# BMS_Interface.net
KiCad netlist of a schematic drawn in EAGLE
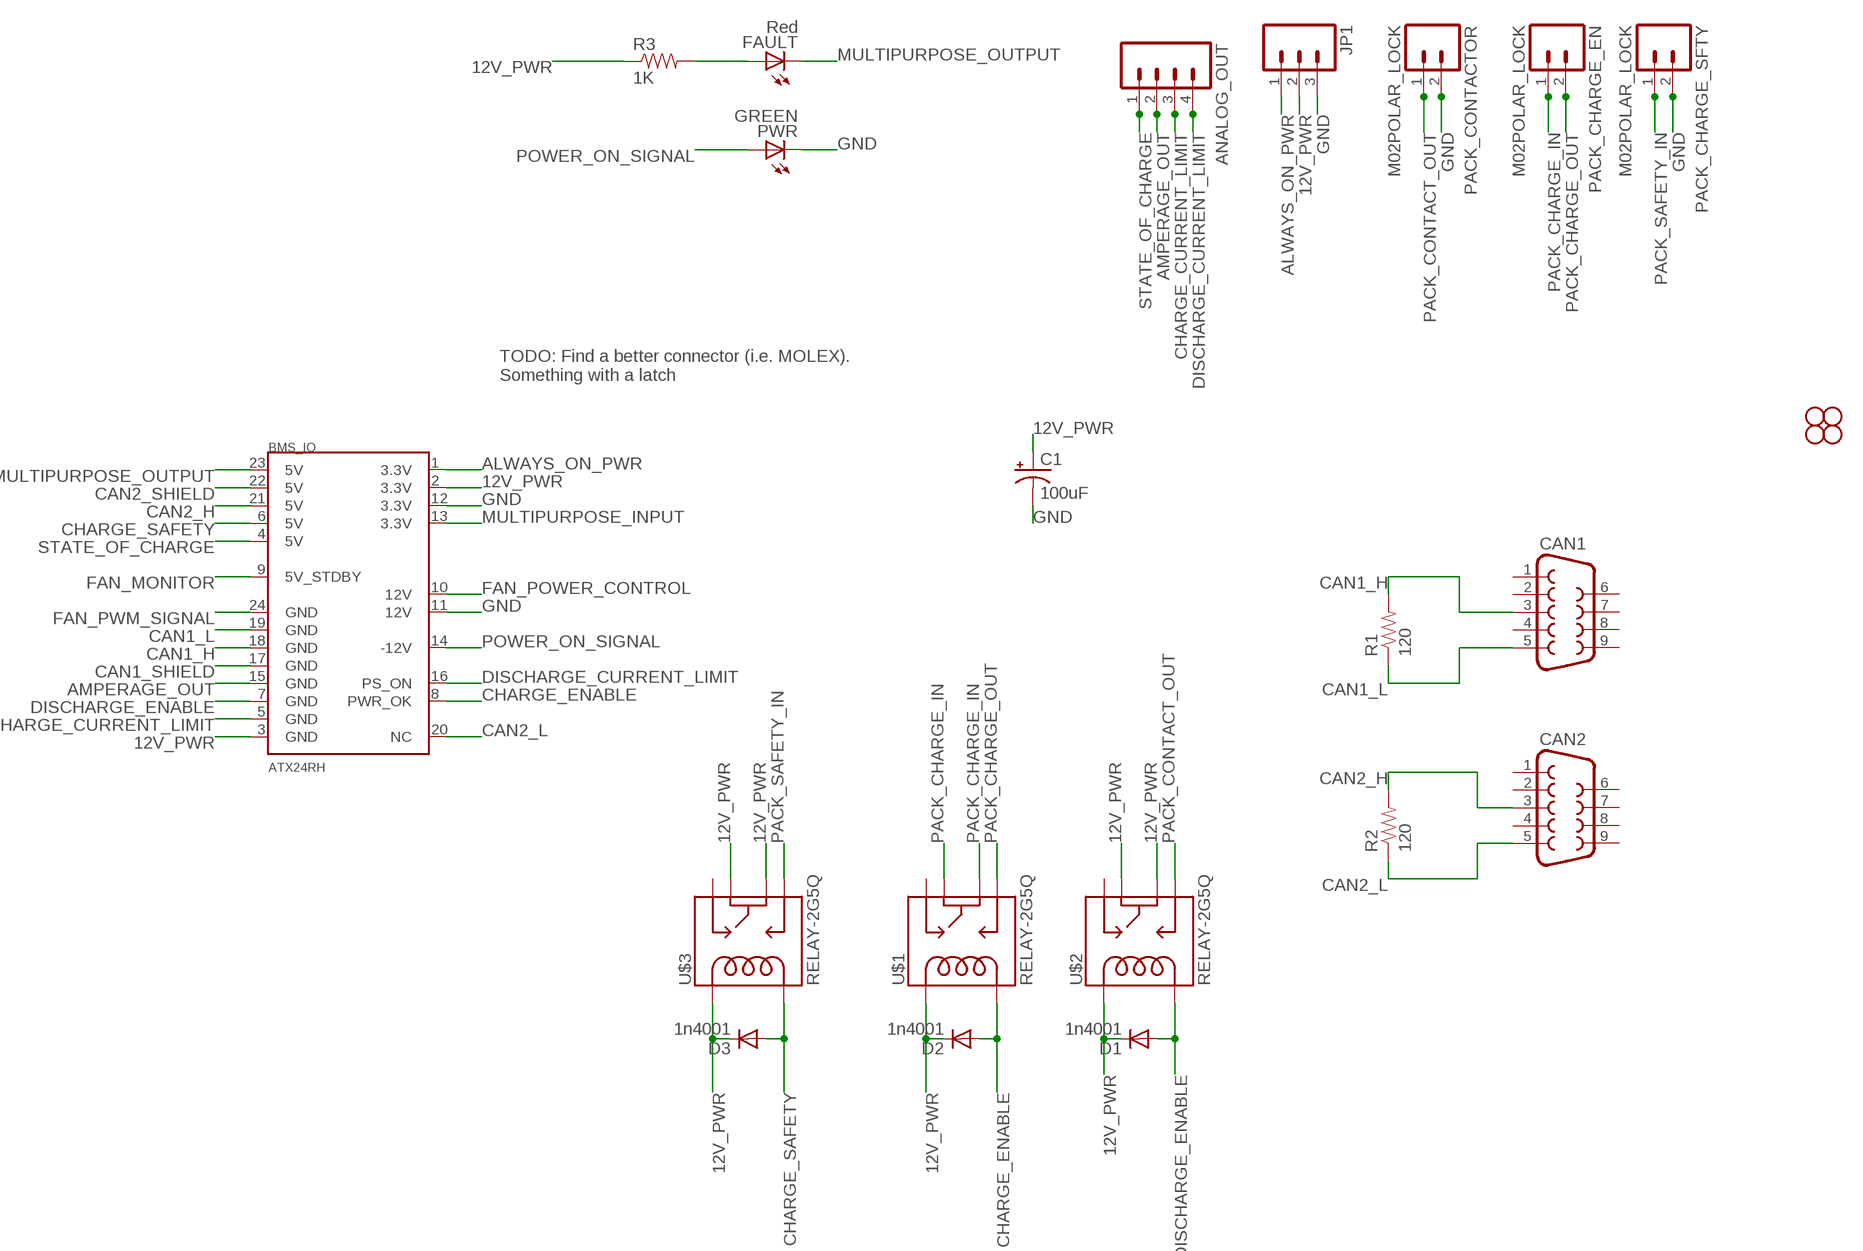
[diagram p0: schematic, sheet 1]

(export (version "E")
  (design (tool "Eeschema 10.0.6"))
  (components
    (comp (ref "ANALOG_OUT")
      (value "M04POLAR_LOCK")
      (footprint "eagle-import:MOLEX-1X4_LOCK")
      (libsource (lib "eagle-import") (part "M04POLAR_LOCK"))
    )
    (comp (ref "BMS_IO")
      (value "ATX24RH")
      (footprint "eagle-import:ATX24_RIGHT_ANGLE")
      (libsource (lib "eagle-import") (part "ATX24RH"))
    )
    (comp (ref "C1")
      (value "100uF")
      (footprint "eagle-import:CPOL-RADIAL-100UF-25V")
      (libsource (lib "eagle-import") (part "CAP_POLPTH1"))
    )
    (comp (ref "CAN1")
      (value "DB9FEMALE")
      (footprint "eagle-import:DB9")
      (libsource (lib "eagle-import") (part "DB9FEMALE"))
    )
    (comp (ref "CAN2")
      (value "DB9FEMALE")
      (footprint "eagle-import:DB9")
      (libsource (lib "eagle-import") (part "DB9FEMALE"))
    )
    (comp (ref "D1")
      (value "1n4001")
      (footprint "eagle-import:SMA-DIODE")
      (libsource (lib "eagle-import") (part "DIODESMA"))
    )
    (comp (ref "D2")
      (value "1n4001")
      (footprint "eagle-import:SMA-DIODE")
      (libsource (lib "eagle-import") (part "DIODESMA"))
    )
    (comp (ref "D3")
      (value "1n4001")
      (footprint "eagle-import:SMA-DIODE")
      (libsource (lib "eagle-import") (part "DIODESMA"))
    )
    (comp (ref "FAULT")
      (value "Red")
      (footprint "eagle-import:LED5MM")
      (libsource (lib "eagle-import") (part "LED5MM"))
    )
    (comp (ref "JP1")
      (value "M03SCREW")
      (footprint "eagle-import:SCREWTERMINAL-3.5MM-3")
      (libsource (lib "eagle-import") (part "M03SCREW"))
    )
    (comp (ref "PACK_CHARGE_EN")
      (value "M02POLAR_LOCK")
      (footprint "eagle-import:MOLEX-1X2_LOCK")
      (libsource (lib "eagle-import") (part "M02POLAR_LOCK"))
    )
    (comp (ref "PACK_CHARGE_SFTY")
      (value "M02POLAR_LOCK")
      (footprint "eagle-import:MOLEX-1X2_LOCK")
      (libsource (lib "eagle-import") (part "M02POLAR_LOCK"))
    )
    (comp (ref "PACK_CONTACTOR")
      (value "M02POLAR_LOCK")
      (footprint "eagle-import:MOLEX-1X2_LOCK")
      (libsource (lib "eagle-import") (part "M02POLAR_LOCK"))
    )
    (comp (ref "PWR")
      (value "GREEN")
      (footprint "eagle-import:LED5MM")
      (libsource (lib "eagle-import") (part "LED5MM"))
    )
    (comp (ref "R1")
      (value "120")
      (footprint "eagle-import:0603-RES")
      (libsource (lib "eagle-import") (part "RESISTOR0603"))
    )
    (comp (ref "R2")
      (value "120")
      (footprint "eagle-import:0603-RES")
      (libsource (lib "eagle-import") (part "RESISTOR0603"))
    )
    (comp (ref "R3")
      (value "1K")
      (footprint "eagle-import:0805")
      (libsource (lib "eagle-import") (part "RESISTOR0805-RES"))
    )
    (comp (ref "STANDOFF1")
      (value "STAND-OFF")
      (footprint "eagle-import:STAND-OFF")
      (libsource (lib "eagle-import") (part "STAND-OFF"))
    )
    (comp (ref "STANDOFF2")
      (value "STAND-OFF")
      (footprint "eagle-import:STAND-OFF")
      (libsource (lib "eagle-import") (part "STAND-OFF"))
    )
    (comp (ref "STANDOFF3")
      (value "STAND-OFF")
      (footprint "eagle-import:STAND-OFF")
      (libsource (lib "eagle-import") (part "STAND-OFF"))
    )
    (comp (ref "STANDOFF4")
      (value "STAND-OFF")
      (footprint "eagle-import:STAND-OFF")
      (libsource (lib "eagle-import") (part "STAND-OFF"))
    )
    (comp (ref "U$1")
      (value "RELAY-2G5Q")
      (footprint "eagle-import:RELAY-G5V")
      (libsource (lib "eagle-import") (part "RELAY-2G5Q"))
    )
    (comp (ref "U$2")
      (value "RELAY-2G5Q")
      (footprint "eagle-import:RELAY-G5V")
      (libsource (lib "eagle-import") (part "RELAY-2G5Q"))
    )
    (comp (ref "U$3")
      (value "RELAY-2G5Q")
      (footprint "eagle-import:RELAY-G5V")
      (libsource (lib "eagle-import") (part "RELAY-2G5Q"))
    )
  )
  (nets
    (net (code "1") (name "/12V_PWR") (class "Default")
      (node (ref "BMS_IO") (pin "2") (pinfunction "3.3V_2") (pintype "bidirectional"))
      (node (ref "BMS_IO") (pin "3") (pinfunction "GND_3") (pintype "bidirectional"))
      (node (ref "C1") (pin "1") (pinfunction "+_1") (pintype "passive"))
      (node (ref "D1") (pin "C") (pinfunction "C_C") (pintype "passive"))
      (node (ref "D2") (pin "C") (pinfunction "C_C") (pintype "passive"))
      (node (ref "D3") (pin "C") (pinfunction "C_C") (pintype "passive"))
      (node (ref "JP1") (pin "2") (pinfunction "2_2") (pintype "passive"))
      (node (ref "R3") (pin "1") (pinfunction "1_1") (pintype "passive"))
      (node (ref "U$1") (pin "2") (pinfunction "2_2") (pintype "bidirectional"))
      (node (ref "U$2") (pin "2") (pinfunction "2_2") (pintype "bidirectional"))
      (node (ref "U$2") (pin "5") (pinfunction "5_5") (pintype "bidirectional"))
      (node (ref "U$2") (pin "6") (pinfunction "6_6") (pintype "bidirectional"))
      (node (ref "U$3") (pin "2") (pinfunction "2_2") (pintype "bidirectional"))
      (node (ref "U$3") (pin "5") (pinfunction "5_5") (pintype "bidirectional"))
      (node (ref "U$3") (pin "6") (pinfunction "6_6") (pintype "bidirectional"))
    )
    (net (code "2") (name "/ALWAYS_ON_PWR") (class "Default")
      (node (ref "BMS_IO") (pin "1") (pinfunction "3.3V_1") (pintype "bidirectional"))
      (node (ref "JP1") (pin "1") (pinfunction "1_1") (pintype "passive"))
    )
    (net (code "3") (name "/AMPERAGE_OUT") (class "Default")
      (node (ref "ANALOG_OUT") (pin "2") (pinfunction "2_2") (pintype "passive"))
      (node (ref "BMS_IO") (pin "15") (pinfunction "GND_15") (pintype "bidirectional"))
    )
    (net (code "4") (name "/CAN1_H") (class "Default")
      (node (ref "BMS_IO") (pin "18") (pinfunction "GND_18") (pintype "bidirectional"))
      (node (ref "CAN1") (pin "3") (pinfunction "3_3") (pintype "passive"))
      (node (ref "R1") (pin "2") (pinfunction "2_2") (pintype "passive"))
    )
    (net (code "5") (name "/CAN1_L") (class "Default")
      (node (ref "BMS_IO") (pin "19") (pinfunction "GND_19") (pintype "bidirectional"))
      (node (ref "CAN1") (pin "5") (pinfunction "5_5") (pintype "passive"))
      (node (ref "R1") (pin "1") (pinfunction "1_1") (pintype "passive"))
    )
    (net (code "6") (name "/CAN1_SHIELD") (class "Default")
      (node (ref "BMS_IO") (pin "17") (pinfunction "GND_17") (pintype "bidirectional"))
    )
    (net (code "7") (name "/CAN2_H") (class "Default")
      (node (ref "BMS_IO") (pin "21") (pinfunction "5V_21") (pintype "bidirectional"))
      (node (ref "CAN2") (pin "3") (pinfunction "3_3") (pintype "passive"))
      (node (ref "R2") (pin "2") (pinfunction "2_2") (pintype "passive"))
    )
    (net (code "8") (name "/CAN2_L") (class "Default")
      (node (ref "BMS_IO") (pin "20") (pinfunction "NC_20") (pintype "bidirectional"))
      (node (ref "CAN2") (pin "5") (pinfunction "5_5") (pintype "passive"))
      (node (ref "R2") (pin "1") (pinfunction "1_1") (pintype "passive"))
    )
    (net (code "9") (name "/CAN2_SHIELD") (class "Default")
      (node (ref "BMS_IO") (pin "22") (pinfunction "5V_22") (pintype "bidirectional"))
    )
    (net (code "10") (name "/CHARGE_CURRENT_LIMIT") (class "Default")
      (node (ref "ANALOG_OUT") (pin "3") (pinfunction "3_3") (pintype "passive"))
      (node (ref "BMS_IO") (pin "5") (pinfunction "GND_5") (pintype "bidirectional"))
    )
    (net (code "11") (name "/CHARGE_ENABLE") (class "Default")
      (node (ref "BMS_IO") (pin "8") (pinfunction "PWR_OK_8") (pintype "bidirectional"))
      (node (ref "D2") (pin "A") (pinfunction "A_A") (pintype "passive"))
      (node (ref "U$1") (pin "9") (pinfunction "9_9") (pintype "bidirectional"))
    )
    (net (code "12") (name "/CHARGE_SAFETY") (class "Default")
      (node (ref "BMS_IO") (pin "6") (pinfunction "5V_6") (pintype "bidirectional"))
      (node (ref "D3") (pin "A") (pinfunction "A_A") (pintype "passive"))
      (node (ref "U$3") (pin "9") (pinfunction "9_9") (pintype "bidirectional"))
    )
    (net (code "13") (name "/DISCHARGE_CURRENT_LIMIT") (class "Default")
      (node (ref "ANALOG_OUT") (pin "4") (pinfunction "4_4") (pintype "passive"))
      (node (ref "BMS_IO") (pin "16") (pinfunction "PS_ON_16") (pintype "bidirectional"))
    )
    (net (code "14") (name "/DISCHARGE_ENABLE") (class "Default")
      (node (ref "BMS_IO") (pin "7") (pinfunction "GND_7") (pintype "bidirectional"))
      (node (ref "D1") (pin "A") (pinfunction "A_A") (pintype "passive"))
      (node (ref "U$2") (pin "9") (pinfunction "9_9") (pintype "bidirectional"))
    )
    (net (code "15") (name "/FAN_MONITOR") (class "Default")
      (node (ref "BMS_IO") (pin "9") (pinfunction "5V_STDBY_9") (pintype "bidirectional"))
    )
    (net (code "16") (name "/FAN_POWER_CONTROL") (class "Default")
      (node (ref "BMS_IO") (pin "10") (pinfunction "12V_10") (pintype "bidirectional"))
    )
    (net (code "17") (name "/FAN_PWM_SIGNAL") (class "Default")
      (node (ref "BMS_IO") (pin "24") (pinfunction "GND_24") (pintype "bidirectional"))
    )
    (net (code "18") (name "/GND") (class "Default")
      (node (ref "BMS_IO") (pin "11") (pinfunction "12V_11") (pintype "bidirectional"))
      (node (ref "BMS_IO") (pin "12") (pinfunction "3.3V_12") (pintype "bidirectional"))
      (node (ref "C1") (pin "2") (pinfunction "-_2") (pintype "passive"))
      (node (ref "JP1") (pin "3") (pinfunction "3_3") (pintype "passive"))
      (node (ref "PACK_CHARGE_SFTY") (pin "2") (pinfunction "2_2") (pintype "passive"))
      (node (ref "PACK_CONTACTOR") (pin "2") (pinfunction "2_2") (pintype "passive"))
      (node (ref "PWR") (pin "K") (pinfunction "C_K") (pintype "passive"))
    )
    (net (code "19") (name "/MULTIPURPOSE_INPUT") (class "Default")
      (node (ref "BMS_IO") (pin "13") (pinfunction "3.3V_13") (pintype "bidirectional"))
    )
    (net (code "20") (name "/MULTIPURPOSE_OUTPUT") (class "Default")
      (node (ref "BMS_IO") (pin "23") (pinfunction "5V_23") (pintype "bidirectional"))
      (node (ref "FAULT") (pin "K") (pinfunction "C_K") (pintype "passive"))
    )
    (net (code "21") (name "/PACK_CHARGE_IN") (class "Default")
      (node (ref "PACK_CHARGE_EN") (pin "1") (pinfunction "1_1") (pintype "passive"))
      (node (ref "U$1") (pin "5") (pinfunction "5_5") (pintype "bidirectional"))
      (node (ref "U$1") (pin "6") (pinfunction "6_6") (pintype "bidirectional"))
    )
    (net (code "22") (name "/PACK_CHARGE_OUT") (class "Default")
      (node (ref "PACK_CHARGE_EN") (pin "2") (pinfunction "2_2") (pintype "passive"))
      (node (ref "U$1") (pin "10") (pinfunction "10_10") (pintype "bidirectional"))
    )
    (net (code "23") (name "/PACK_CONTACT_OUT") (class "Default")
      (node (ref "PACK_CONTACTOR") (pin "1") (pinfunction "1_1") (pintype "passive"))
      (node (ref "U$2") (pin "10") (pinfunction "10_10") (pintype "bidirectional"))
    )
    (net (code "24") (name "/PACK_SAFETY_IN") (class "Default")
      (node (ref "PACK_CHARGE_SFTY") (pin "1") (pinfunction "1_1") (pintype "passive"))
      (node (ref "U$3") (pin "10") (pinfunction "10_10") (pintype "bidirectional"))
    )
    (net (code "25") (name "/POWER_ON_SIGNAL") (class "Default")
      (node (ref "BMS_IO") (pin "14") (pinfunction "-12V_14") (pintype "bidirectional"))
      (node (ref "PWR") (pin "A") (pinfunction "A_A") (pintype "passive"))
    )
    (net (code "26") (name "/STATE_OF_CHARGE") (class "Default")
      (node (ref "ANALOG_OUT") (pin "1") (pinfunction "1_1") (pintype "passive"))
      (node (ref "BMS_IO") (pin "4") (pinfunction "5V_4") (pintype "bidirectional"))
    )
    (net (code "27") (name "Net-(FAULT-PadA)") (class "Default")
      (node (ref "FAULT") (pin "A") (pinfunction "A_A") (pintype "passive"))
      (node (ref "R3") (pin "2") (pinfunction "2_2") (pintype "passive"))
    )
    (net (code "28") (name "unconnected-(CAN1-Pad1)") (class "Default")
      (node (ref "CAN1") (pin "1") (pinfunction "1_1") (pintype "passive"))
    )
    (net (code "29") (name "unconnected-(CAN1-Pad2)") (class "Default")
      (node (ref "CAN1") (pin "2") (pinfunction "2_2") (pintype "passive"))
    )
    (net (code "30") (name "unconnected-(CAN1-Pad4)") (class "Default")
      (node (ref "CAN1") (pin "4") (pinfunction "4_4") (pintype "passive"))
    )
    (net (code "31") (name "unconnected-(CAN1-Pad6)") (class "Default")
      (node (ref "CAN1") (pin "6") (pinfunction "6_6") (pintype "passive"))
    )
    (net (code "32") (name "unconnected-(CAN1-Pad7)") (class "Default")
      (node (ref "CAN1") (pin "7") (pinfunction "7_7") (pintype "passive"))
    )
    (net (code "33") (name "unconnected-(CAN1-Pad8)") (class "Default")
      (node (ref "CAN1") (pin "8") (pinfunction "8_8") (pintype "passive"))
    )
    (net (code "34") (name "unconnected-(CAN1-Pad9)") (class "Default")
      (node (ref "CAN1") (pin "9") (pinfunction "9_9") (pintype "passive"))
    )
    (net (code "35") (name "unconnected-(CAN2-Pad1)") (class "Default")
      (node (ref "CAN2") (pin "1") (pinfunction "1_1") (pintype "passive"))
    )
    (net (code "36") (name "unconnected-(CAN2-Pad2)") (class "Default")
      (node (ref "CAN2") (pin "2") (pinfunction "2_2") (pintype "passive"))
    )
    (net (code "37") (name "unconnected-(CAN2-Pad4)") (class "Default")
      (node (ref "CAN2") (pin "4") (pinfunction "4_4") (pintype "passive"))
    )
    (net (code "38") (name "unconnected-(CAN2-Pad6)") (class "Default")
      (node (ref "CAN2") (pin "6") (pinfunction "6_6") (pintype "passive"))
    )
    (net (code "39") (name "unconnected-(CAN2-Pad7)") (class "Default")
      (node (ref "CAN2") (pin "7") (pinfunction "7_7") (pintype "passive"))
    )
    (net (code "40") (name "unconnected-(CAN2-Pad8)") (class "Default")
      (node (ref "CAN2") (pin "8") (pinfunction "8_8") (pintype "passive"))
    )
    (net (code "41") (name "unconnected-(CAN2-Pad9)") (class "Default")
      (node (ref "CAN2") (pin "9") (pinfunction "9_9") (pintype "passive"))
    )
    (net (code "42") (name "unconnected-(U$1-Pad1)") (class "Default")
      (node (ref "U$1") (pin "1") (pinfunction "1_1") (pintype "bidirectional"))
    )
    (net (code "43") (name "unconnected-(U$2-Pad1)") (class "Default")
      (node (ref "U$2") (pin "1") (pinfunction "1_1") (pintype "bidirectional"))
    )
    (net (code "44") (name "unconnected-(U$3-Pad1)") (class "Default")
      (node (ref "U$3") (pin "1") (pinfunction "1_1") (pintype "bidirectional"))
    )
  )
)
